# Temperature_Control_LAB_ESP32.net
KiCad netlist of a schematic drawn in EAGLE
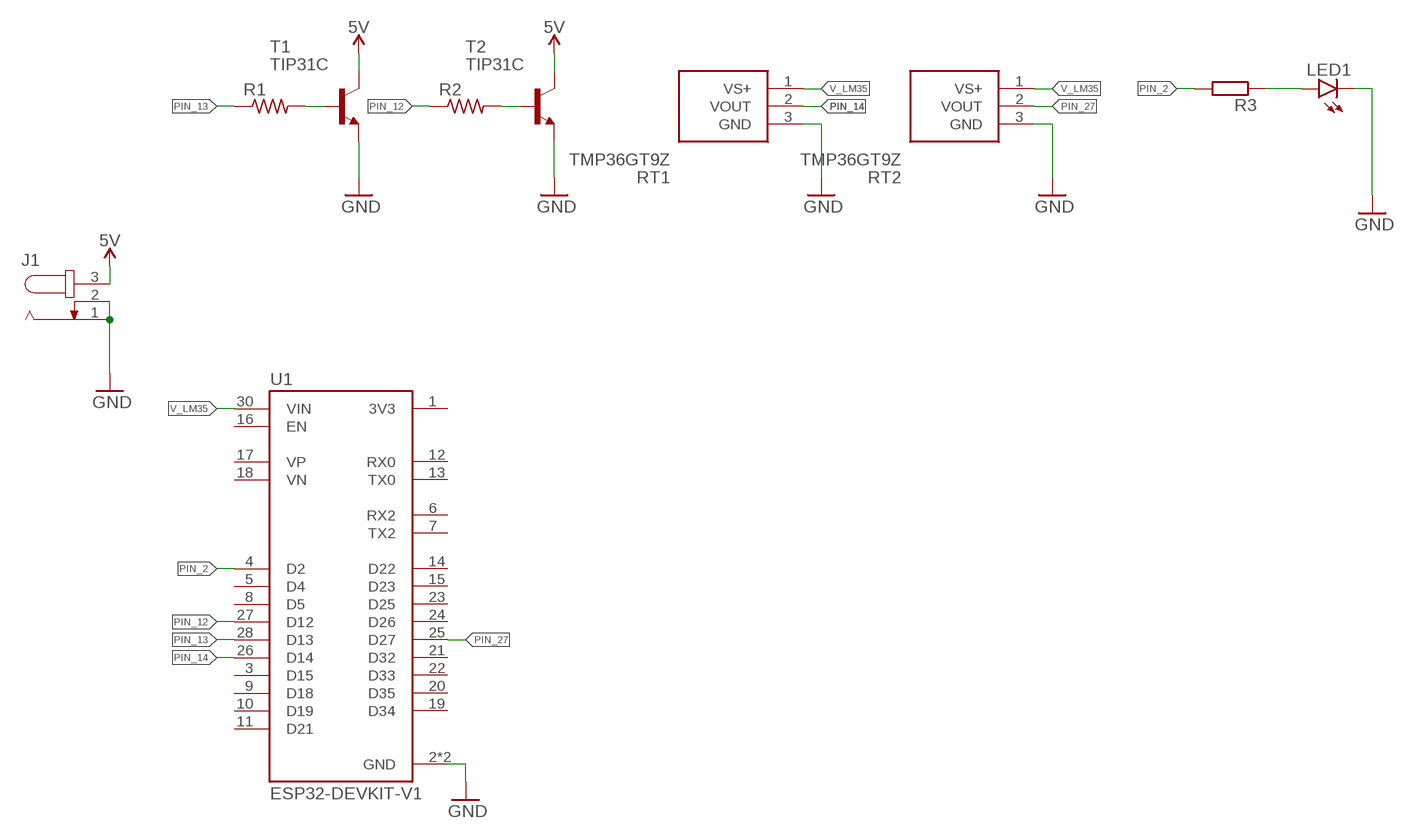
[diagram p0: schematic, sheet 1]

(export (version "E")
  (design (tool "Eeschema 10.0.6"))
  (components
    (comp (ref "J1")
      (value "JACK-PLUG0")
      (footprint "eagle-import:SPC4077")
      (libsource (lib "eagle-import") (part "JACK-PLUG0"))
    )
    (comp (ref "LED1")
      (value "LED5MM")
      (footprint "eagle-import:LED5MM")
      (libsource (lib "eagle-import") (part "LED5MM"))
    )
    (comp (ref "R1")
      (value "R-US_M0805")
      (footprint "eagle-import:M0805")
      (libsource (lib "eagle-import") (part "R-US_M0805"))
    )
    (comp (ref "R2")
      (value "R-US_M0805")
      (footprint "eagle-import:M0805")
      (libsource (lib "eagle-import") (part "R-US_M0805"))
    )
    (comp (ref "R3")
      (value "R-EU_R0805")
      (footprint "eagle-import:R0805")
      (libsource (lib "eagle-import") (part "R-EU_R0805"))
    )
    (comp (ref "RT1")
      (value "TMP36GT9Z")
      (footprint "eagle-import:TO-92")
      (fields (field (name "MOUSER_PART_NUMBER") "584-TMP36GT9Z"))
      (libsource (lib "eagle-import") (part "TMP36GT9Z"))
    )
    (comp (ref "RT2")
      (value "TMP36GT9Z")
      (footprint "eagle-import:TO-92")
      (fields (field (name "MOUSER_PART_NUMBER") "584-TMP36GT9Z"))
      (libsource (lib "eagle-import") (part "TMP36GT9Z"))
    )
    (comp (ref "T1")
      (value "TIP31C")
      (footprint "eagle-import:TO220")
      (fields (field (name "MF") "STMicroelectronics"))
      (libsource (lib "eagle-import") (part "TIP31C"))
    )
    (comp (ref "T2")
      (value "TIP31C")
      (footprint "eagle-import:TO220")
      (fields (field (name "MF") "STMicroelectronics"))
      (libsource (lib "eagle-import") (part "TIP31C"))
    )
    (comp (ref "U1")
      (value "ESP32-DEVKIT-V1")
      (footprint "eagle-import:MODULE_ESP32_DEVKIT_V1")
      (fields (field (name "MF") "Do it"))
      (libsource (lib "eagle-import") (part "ESP32-DEVKIT-V1"))
    )
  )
  (nets
    (net (code "1") (name "5V") (class "Default")
      (node (ref "J1") (pin "3") (pinfunction "3_3") (pintype "passive"))
      (node (ref "T1") (pin "2") (pinfunction "C_2") (pintype "passive"))
      (node (ref "T2") (pin "2") (pinfunction "C_2") (pintype "passive"))
    )
    (net (code "2") (name "GND") (class "Default")
      (node (ref "J1") (pin "1") (pinfunction "1_1") (pintype "passive"))
      (node (ref "J1") (pin "2") (pinfunction "2_2") (pintype "passive"))
      (node (ref "LED1") (pin "K") (pinfunction "C_K") (pintype "passive"))
      (node (ref "RT1") (pin "3") (pinfunction "GND_3") (pintype "power_in"))
      (node (ref "RT2") (pin "3") (pinfunction "GND_3") (pintype "power_in"))
      (node (ref "T1") (pin "3") (pinfunction "E_3") (pintype "passive"))
      (node (ref "T2") (pin "3") (pinfunction "E_3") (pintype "passive"))
      (node (ref "U1") (pin "2") (pinfunction "GND_2") (pintype "power_in"))
      (node (ref "U1") (pin "29") (pinfunction "GND_29") (pintype "power_in"))
    )
    (net (code "3") (name "Net-(LED1-PadA)") (class "Default")
      (node (ref "LED1") (pin "A") (pinfunction "A_A") (pintype "passive"))
      (node (ref "R3") (pin "1") (pinfunction "1_1") (pintype "passive"))
    )
    (net (code "4") (name "Net-(T1-B)") (class "Default")
      (node (ref "R1") (pin "2") (pinfunction "2_2") (pintype "passive"))
      (node (ref "T1") (pin "1") (pinfunction "B_1") (pintype "passive"))
    )
    (net (code "5") (name "Net-(T2-B)") (class "Default")
      (node (ref "R2") (pin "2") (pinfunction "2_2") (pintype "passive"))
      (node (ref "T2") (pin "1") (pinfunction "B_1") (pintype "passive"))
    )
    (net (code "6") (name "PIN_2") (class "Default")
      (node (ref "R3") (pin "2") (pinfunction "2_2") (pintype "passive"))
      (node (ref "U1") (pin "4") (pinfunction "D2_4") (pintype "bidirectional"))
    )
    (net (code "7") (name "PIN_12") (class "Default")
      (node (ref "R2") (pin "1") (pinfunction "1_1") (pintype "passive"))
      (node (ref "U1") (pin "27") (pinfunction "D12_27") (pintype "bidirectional"))
    )
    (net (code "8") (name "PIN_13") (class "Default")
      (node (ref "R1") (pin "1") (pinfunction "1_1") (pintype "passive"))
      (node (ref "U1") (pin "28") (pinfunction "D13_28") (pintype "bidirectional"))
    )
    (net (code "9") (name "PIN_14") (class "Default")
      (node (ref "RT1") (pin "2") (pinfunction "VOUT_2") (pintype "output"))
      (node (ref "U1") (pin "26") (pinfunction "D14_26") (pintype "bidirectional"))
    )
    (net (code "10") (name "PIN_27") (class "Default")
      (node (ref "RT2") (pin "2") (pinfunction "VOUT_2") (pintype "output"))
      (node (ref "U1") (pin "25") (pinfunction "D27_25") (pintype "bidirectional"))
    )
    (net (code "11") (name "V_LM35") (class "Default")
      (node (ref "RT1") (pin "1") (pinfunction "VS+_1") (pintype "power_in"))
      (node (ref "RT2") (pin "1") (pinfunction "VS+_1") (pintype "power_in"))
      (node (ref "U1") (pin "30") (pinfunction "VIN_30") (pintype "input"))
    )
    (net (code "12") (name "unconnected-(U1-3V3-Pad1)") (class "Default")
      (node (ref "U1") (pin "1") (pinfunction "3V3_1") (pintype "output"))
    )
    (net (code "13") (name "unconnected-(U1-D4-Pad5)") (class "Default")
      (node (ref "U1") (pin "5") (pinfunction "D4_5") (pintype "bidirectional"))
    )
    (net (code "14") (name "unconnected-(U1-D5-Pad8)") (class "Default")
      (node (ref "U1") (pin "8") (pinfunction "D5_8") (pintype "bidirectional"))
    )
    (net (code "15") (name "unconnected-(U1-D15-Pad3)") (class "Default")
      (node (ref "U1") (pin "3") (pinfunction "D15_3") (pintype "bidirectional"))
    )
    (net (code "16") (name "unconnected-(U1-D18-Pad9)") (class "Default")
      (node (ref "U1") (pin "9") (pinfunction "D18_9") (pintype "bidirectional"))
    )
    (net (code "17") (name "unconnected-(U1-D19-Pad10)") (class "Default")
      (node (ref "U1") (pin "10") (pinfunction "D19_10") (pintype "bidirectional"))
    )
    (net (code "18") (name "unconnected-(U1-D21-Pad11)") (class "Default")
      (node (ref "U1") (pin "11") (pinfunction "D21_11") (pintype "bidirectional"))
    )
    (net (code "19") (name "unconnected-(U1-D22-Pad14)") (class "Default")
      (node (ref "U1") (pin "14") (pinfunction "D22_14") (pintype "bidirectional"))
    )
    (net (code "20") (name "unconnected-(U1-D23-Pad15)") (class "Default")
      (node (ref "U1") (pin "15") (pinfunction "D23_15") (pintype "bidirectional"))
    )
    (net (code "21") (name "unconnected-(U1-D25-Pad23)") (class "Default")
      (node (ref "U1") (pin "23") (pinfunction "D25_23") (pintype "bidirectional"))
    )
    (net (code "22") (name "unconnected-(U1-D26-Pad24)") (class "Default")
      (node (ref "U1") (pin "24") (pinfunction "D26_24") (pintype "bidirectional"))
    )
    (net (code "23") (name "unconnected-(U1-D32-Pad21)") (class "Default")
      (node (ref "U1") (pin "21") (pinfunction "D32_21") (pintype "bidirectional"))
    )
    (net (code "24") (name "unconnected-(U1-D33-Pad22)") (class "Default")
      (node (ref "U1") (pin "22") (pinfunction "D33_22") (pintype "bidirectional"))
    )
    (net (code "25") (name "unconnected-(U1-D34-Pad19)") (class "Default")
      (node (ref "U1") (pin "19") (pinfunction "D34_19") (pintype "bidirectional"))
    )
    (net (code "26") (name "unconnected-(U1-D35-Pad20)") (class "Default")
      (node (ref "U1") (pin "20") (pinfunction "D35_20") (pintype "bidirectional"))
    )
    (net (code "27") (name "unconnected-(U1-EN-Pad16)") (class "Default")
      (node (ref "U1") (pin "16") (pinfunction "EN_16") (pintype "input"))
    )
    (net (code "28") (name "unconnected-(U1-RX0-Pad12)") (class "Default")
      (node (ref "U1") (pin "12") (pinfunction "RX0_12") (pintype "input"))
    )
    (net (code "29") (name "unconnected-(U1-RX2-Pad6)") (class "Default")
      (node (ref "U1") (pin "6") (pinfunction "RX2_6") (pintype "input"))
    )
    (net (code "30") (name "unconnected-(U1-TX0-Pad13)") (class "Default")
      (node (ref "U1") (pin "13") (pinfunction "TX0_13") (pintype "output"))
    )
    (net (code "31") (name "unconnected-(U1-TX2-Pad7)") (class "Default")
      (node (ref "U1") (pin "7") (pinfunction "TX2_7") (pintype "output"))
    )
    (net (code "32") (name "unconnected-(U1-VN-Pad18)") (class "Default")
      (node (ref "U1") (pin "18") (pinfunction "VN_18") (pintype "bidirectional"))
    )
    (net (code "33") (name "unconnected-(U1-VP-Pad17)") (class "Default")
      (node (ref "U1") (pin "17") (pinfunction "VP_17") (pintype "bidirectional"))
    )
  )
)
